# 2_cubesat_bus.net
KiCad netlist of a schematic drawn in Altium Designer
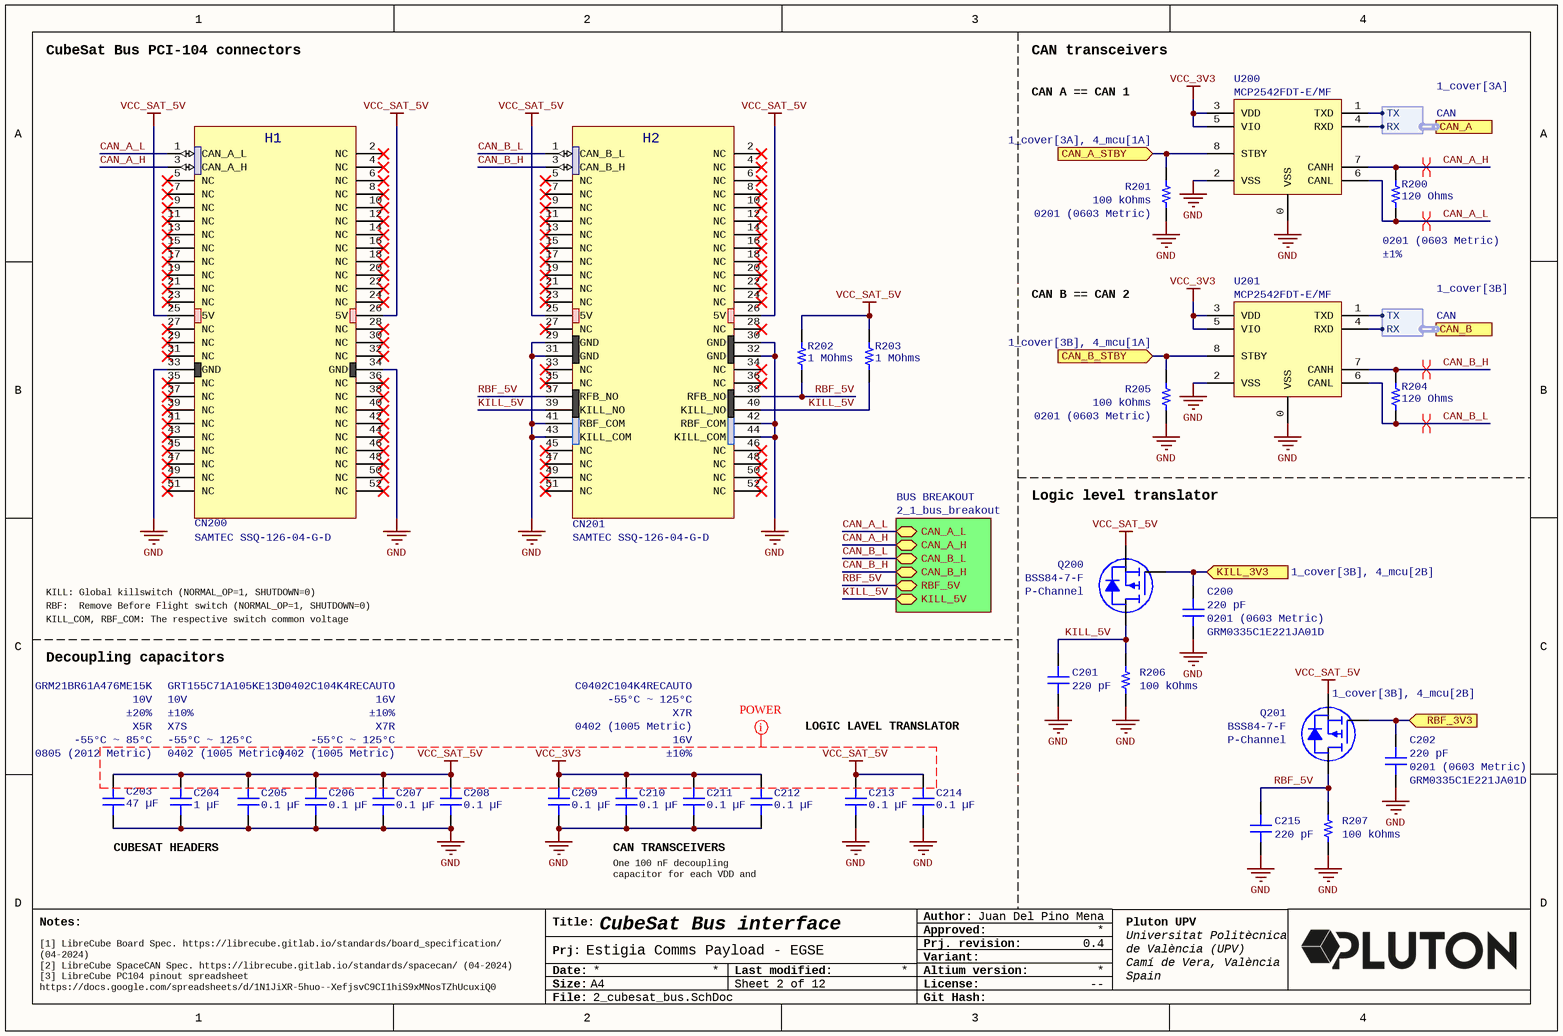
[diagram p0: 2_cubesat_bus.SchDoc]

(export (version "E")
  (design (tool "Eeschema 10.0.6"))
  (components
    (comp (ref "C200")
      (value "220 pF")
      (footprint "CAP 0201_0603")
      (description "CAP CER 220PF 25V C0G/NP0 0201")
      (fields
        (field (name "PART NUMBER") "GRM0335C1E221JA01D")
        (field (name "DEVICE PACKAGE") "0201 (0603 Metric)")
        (field (name "MANUFACTURER") "Murata Electronics")
        (field (name "TOLERANCE") "±5%")
      )
      (libsource (lib "Celestial Altium Library - altium_library") (part "Capacitor"))
    )
    (comp (ref "C201")
      (value "220 pF")
      (footprint "CAP 0201_0603")
      (description "CAP CER 220PF 25V C0G/NP0 0201")
      (fields
        (field (name "PART NUMBER") "GRM0335C1E221JA01D")
        (field (name "MANUFACTURER") "Murata Electronics")
      )
      (libsource (lib "Celestial Altium Library - altium_library") (part "Capacitor"))
    )
    (comp (ref "C202")
      (value "220 pF")
      (footprint "CAP 0201_0603")
      (description "CAP CER 220PF 25V C0G/NP0 0201")
      (fields
        (field (name "PART NUMBER") "GRM0335C1E221JA01D")
        (field (name "DEVICE PACKAGE") "0201 (0603 Metric)")
        (field (name "MANUFACTURER") "Murata Electronics")
        (field (name "TOLERANCE") "±5%")
      )
      (libsource (lib "Celestial Altium Library - altium_library") (part "Capacitor"))
    )
    (comp (ref "C203")
      (value "47 µF")
      (footprint "CAP 0805_2012")
      (description "CAP CER 47UF 10V X5R 0805")
      (fields
        (field (name "PART NUMBER") "GRM21BR61A476ME15K")
        (field (name "DEVICE PACKAGE") "0805 (2012 Metric)")
        (field (name "MANUFACTURER") "Murata Electronics")
        (field (name "OPERATING TEMPERATURE") "-55°C ~ 85°C")
        (field (name "TEMPERATURE COEFFICIENT") "X5R")
        (field (name "TOLERANCE") "±20%")
        (field (name "VOLTAGE - RATED") "10V")
      )
      (libsource (lib "Celestial Altium Library - altium_library") (part "Capacitor"))
    )
    (comp (ref "C204")
      (value "1 µF")
      (footprint "CAP 0402_1005")
      (description "CAP CER 1UF 10V X7S 0402")
      (fields
        (field (name "PART NUMBER") "GRT155C71A105KE13D")
        (field (name "DEVICE PACKAGE") "0402 (1005 Metric)")
        (field (name "MANUFACTURER") "Murata Electronics")
        (field (name "OPERATING TEMPERATURE") "-55°C ~ 125°C")
        (field (name "TEMPERATURE COEFFICIENT") "X7S")
        (field (name "TOLERANCE") "±10%")
        (field (name "VOLTAGE - RATED") "10V")
      )
      (libsource (lib "Celestial Altium Library - altium_library") (part "Capacitor"))
    )
    (comp (ref "C205")
      (value "0.1 µF")
      (footprint "CAP 0402_1005")
      (description "CAP CER 0402 0.1UF 16V X7R 10%")
      (fields
        (field (name "PART NUMBER") "C0402C104K4RECAUTO")
        (field (name "MANUFACTURER") "KEMET")
        (field (name "OPERATING TEMPERATURE") "-55°C ~ 125°C")
        (field (name "PACKAGE / CASE") "0402 (1005 Metric)")
        (field (name "TEMPERATURE COEFFICIENT") "X7R")
        (field (name "TOLERANCE") "±10%")
        (field (name "VOLTAGE - RATED") "16V")
      )
      (libsource (lib "Celestial Altium Library - altium_library") (part "Capacitor"))
    )
    (comp (ref "C206")
      (value "0.1 µF")
      (footprint "CAP 0402_1005")
      (description "CAP CER 0402 0.1UF 16V X7R 10%")
      (fields (field (name "PART NUMBER") "C0402C104K4RECAUTO") (field (name "MANUFACTURER") "KEMET"))
      (libsource (lib "Celestial Altium Library - altium_library") (part "Capacitor"))
    )
    (comp (ref "C207")
      (value "0.1 µF")
      (footprint "CAP 0402_1005")
      (description "CAP CER 0402 0.1UF 16V X7R 10%")
      (fields (field (name "PART NUMBER") "C0402C104K4RECAUTO") (field (name "MANUFACTURER") "KEMET"))
      (libsource (lib "Celestial Altium Library - altium_library") (part "Capacitor"))
    )
    (comp (ref "C208")
      (value "0.1 µF")
      (footprint "CAP 0402_1005")
      (description "CAP CER 0402 0.1UF 16V X7R 10%")
      (fields (field (name "PART NUMBER") "C0402C104K4RECAUTO") (field (name "MANUFACTURER") "KEMET"))
      (libsource (lib "Celestial Altium Library - altium_library") (part "Capacitor"))
    )
    (comp (ref "C209")
      (value "0.1 µF")
      (footprint "CAP 0402_1005")
      (description "CAP CER 0402 0.1UF 16V X7R 10%")
      (fields (field (name "PART NUMBER") "C0402C104K4RECAUTO") (field (name "MANUFACTURER") "KEMET"))
      (libsource (lib "Celestial Altium Library - altium_library") (part "Capacitor"))
    )
    (comp (ref "C210")
      (value "0.1 µF")
      (footprint "CAP 0402_1005")
      (description "CAP CER 0402 0.1UF 16V X7R 10%")
      (fields
        (field (name "PART NUMBER") "C0402C104K4RECAUTO")
        (field (name "MANUFACTURER") "KEMET")
        (field (name "OPERATING TEMPERATURE") "-55°C ~ 125°C")
        (field (name "PACKAGE / CASE") "0402 (1005 Metric)")
        (field (name "TEMPERATURE COEFFICIENT") "X7R")
        (field (name "TOLERANCE") "±10%")
        (field (name "VOLTAGE - RATED") "16V")
      )
      (libsource (lib "Celestial Altium Library - altium_library") (part "Capacitor"))
    )
    (comp (ref "C211")
      (value "0.1 µF")
      (footprint "CAP 0402_1005")
      (description "CAP CER 0402 0.1UF 16V X7R 10%")
      (fields (field (name "PART NUMBER") "C0402C104K4RECAUTO") (field (name "MANUFACTURER") "KEMET"))
      (libsource (lib "Celestial Altium Library - altium_library") (part "Capacitor"))
    )
    (comp (ref "C212")
      (value "0.1 µF")
      (footprint "CAP 0402_1005")
      (description "CAP CER 0402 0.1UF 16V X7R 10%")
      (fields (field (name "PART NUMBER") "C0402C104K4RECAUTO") (field (name "MANUFACTURER") "KEMET"))
      (libsource (lib "Celestial Altium Library - altium_library") (part "Capacitor"))
    )
    (comp (ref "C213")
      (value "0.1 µF")
      (footprint "CAP 0402_1005")
      (description "CAP CER 0402 0.1UF 16V X7R 10%")
      (fields (field (name "PART NUMBER") "C0402C104K4RECAUTO") (field (name "MANUFACTURER") "KEMET"))
      (libsource (lib "Celestial Altium Library - altium_library") (part "Capacitor"))
    )
    (comp (ref "C214")
      (value "0.1 µF")
      (footprint "CAP 0402_1005")
      (description "CAP CER 0402 0.1UF 16V X7R 10%")
      (fields (field (name "PART NUMBER") "C0402C104K4RECAUTO") (field (name "MANUFACTURER") "KEMET"))
      (libsource (lib "Celestial Altium Library - altium_library") (part "Capacitor"))
    )
    (comp (ref "C215")
      (value "220 pF")
      (footprint "CAP 0201_0603")
      (description "CAP CER 220PF 25V C0G/NP0 0201")
      (fields
        (field (name "PART NUMBER") "GRM0335C1E221JA01D")
        (field (name "MANUFACTURER") "Murata Electronics")
      )
      (libsource (lib "Celestial Altium Library - altium_library") (part "Capacitor"))
    )
    (comp (ref "CN200")
      (value "SAMTEC SSQ-126-04-G-D")
      (footprint "connectors:SAMTEC SSQ-126-04-G-D")
      (description "LoRa Payload only pins SAMTEC SSQ-126-04-G-D")
      (libsource (lib "cubesat_bus") (part "CubeSat Header H1 LoRa PL"))
    )
    (comp (ref "CN201")
      (value "SAMTEC SSQ-126-04-G-D")
      (footprint "connectors:SAMTEC SSQ-126-04-G-D")
      (description "LoRa Payload only pins")
      (libsource (lib "cubesat_bus") (part "CubeSat Header H2 LoRa PL"))
    )
    (comp (ref "Q200")
      (value "BSS84-7-F")
      (footprint "DIODES SOT-23-3")
      (description "MOSFET P-CH 50V 130MA SOT23-3")
      (fields
        (field (name "PART NUMBER") "BSS84-7-F")
        (field (name "FET TYPE") "P-Channel")
        (field (name "MANUFACTURER") "Diodes Incorporated")
      )
      (libsource (lib "Celestial Altium Library - altium_library") (part "DIODES MOSFET P-CH SOT-23-3"))
    )
    (comp (ref "Q201")
      (value "BSS84-7-F")
      (footprint "DIODES SOT-23-3")
      (description "MOSFET P-CH 50V 130MA SOT23-3")
      (fields
        (field (name "PART NUMBER") "BSS84-7-F")
        (field (name "FET TYPE") "P-Channel")
        (field (name "MANUFACTURER") "Diodes Incorporated")
      )
      (libsource (lib "Celestial Altium Library - altium_library") (part "DIODES MOSFET P-CH SOT-23-3"))
    )
    (comp (ref "R200")
      (value "120 Ohms")
      (footprint "RES 0201_0603")
      (description "RES SMD 120 OHM 1% 1/20W 0201")
      (fields
        (field (name "PART NUMBER") "CRCW0201120RFNED")
        (field (name "DEVICE PACKAGE") "0201 (0603 Metric)")
        (field (name "MANUFACTURER") "Vishay Dale")
        (field (name "TOLERANCE") "±1%")
      )
      (libsource (lib "Celestial Altium Library - altium_library") (part "Resistor"))
    )
    (comp (ref "R201")
      (value "100 kOhms")
      (footprint "RES 0201_0603")
      (description "RES 100K OHM 1% 1/20W 0201")
      (fields
        (field (name "PART NUMBER") "RC0201FR-13100KL")
        (field (name "DEVICE PACKAGE") "0201 (0603 Metric)")
        (field (name "MANUFACTURER") "Yageo")
      )
      (libsource (lib "Celestial Altium Library - altium_library") (part "Resistor"))
    )
    (comp (ref "R202")
      (value "1 MOhms")
      (footprint "RES 0201_0603")
      (description "RES SMD 1M OHM 5% 1/20W 0201")
      (fields (field (name "PART NUMBER") "CRCW02011M00JNED") (field (name "MANUFACTURER") "Vishay Dale"))
      (libsource (lib "Celestial Altium Library - altium_library") (part "Resistor"))
    )
    (comp (ref "R203")
      (value "1 MOhms")
      (footprint "RES 0201_0603")
      (description "RES SMD 1M OHM 5% 1/20W 0201")
      (fields (field (name "PART NUMBER") "CRCW02011M00JNED") (field (name "MANUFACTURER") "Vishay Dale"))
      (libsource (lib "Celestial Altium Library - altium_library") (part "Resistor"))
    )
    (comp (ref "R204")
      (value "120 Ohms")
      (footprint "RES 0201_0603")
      (description "RES SMD 120 OHM 1% 1/20W 0201")
      (fields (field (name "PART NUMBER") "CRCW0201120RFNED") (field (name "MANUFACTURER") "Vishay Dale"))
      (libsource (lib "Celestial Altium Library - altium_library") (part "Resistor"))
    )
    (comp (ref "R205")
      (value "100 kOhms")
      (footprint "RES 0201_0603")
      (description "RES 100K OHM 1% 1/20W 0201")
      (fields
        (field (name "PART NUMBER") "RC0201FR-13100KL")
        (field (name "DEVICE PACKAGE") "0201 (0603 Metric)")
        (field (name "MANUFACTURER") "Yageo")
      )
      (libsource (lib "Celestial Altium Library - altium_library") (part "Resistor"))
    )
    (comp (ref "R206")
      (value "100 kOhms")
      (footprint "RES 0201_0603")
      (description "RES 100K OHM 1% 1/20W 0201")
      (fields (field (name "PART NUMBER") "RC0201FR-13100KL") (field (name "MANUFACTURER") "Yageo"))
      (libsource (lib "Celestial Altium Library - altium_library") (part "Resistor"))
    )
    (comp (ref "R207")
      (value "100 kOhms")
      (footprint "RES 0201_0603")
      (description "RES 100K OHM 1% 1/20W 0201")
      (fields (field (name "PART NUMBER") "RC0201FR-13100KL") (field (name "MANUFACTURER") "Yageo"))
      (libsource (lib "Celestial Altium Library - altium_library") (part "Resistor"))
    )
    (comp (ref "U200")
      (value "MCP2542FDT-E/MF")
      (footprint "ics:DFN-8 3x3mm")
      (description "IC TRANSCEIVER 1/1 8DFN")
      (fields
        (field (name "MANUFACTURER") "Microchip Technology")
        (field (name "PART NUMBER") "MCP2542FDT-E/MF")
      )
      (libsource (lib "logic") (part "CAN MCP2542FDT-E/MF"))
    )
    (comp (ref "U201")
      (value "MCP2542FDT-E/MF")
      (footprint "ics:DFN-8 3x3mm")
      (description "IC TRANSCEIVER 1/1 8DFN")
      (fields
        (field (name "MANUFACTURER") "Microchip Technology")
        (field (name "PART NUMBER") "MCP2542FDT-E/MF")
      )
      (libsource (lib "logic") (part "CAN MCP2542FDT-E/MF"))
    )
  )
  (nets
    (net (code "2") (name "/CAN_A_H") (class "Default")
      (node (ref "CN200") (pin "3") (pinfunction "CAN_A_H_3") (pintype "bidirectional"))
      (node (ref "R200") (pin "2") (pinfunction "2_2") (pintype "passive"))
      (node (ref "U200") (pin "7") (pinfunction "CANH_7") (pintype "passive"))
    )
    (net (code "3") (name "/CAN_A_L") (class "Default")
      (node (ref "CN200") (pin "1") (pinfunction "CAN_A_L_1") (pintype "bidirectional"))
      (node (ref "R200") (pin "1") (pinfunction "1_1") (pintype "passive"))
      (node (ref "U200") (pin "6") (pinfunction "CANL_6") (pintype "passive"))
    )
    (net (code "4") (name "/CAN_A_STBY") (class "Default")
      (node (ref "R201") (pin "2") (pinfunction "2_2") (pintype "passive"))
      (node (ref "U200") (pin "8") (pinfunction "STBY_8") (pintype "passive"))
    )
    (net (code "5") (name "/CAN_B_H") (class "Default")
      (node (ref "CN201") (pin "3") (pinfunction "CAN_B_H_3") (pintype "bidirectional"))
      (node (ref "R204") (pin "2") (pinfunction "2_2") (pintype "passive"))
      (node (ref "U201") (pin "7") (pinfunction "CANH_7") (pintype "passive"))
    )
    (net (code "6") (name "/CAN_B_L") (class "Default")
      (node (ref "CN201") (pin "1") (pinfunction "CAN_B_L_1") (pintype "bidirectional"))
      (node (ref "R204") (pin "1") (pinfunction "1_1") (pintype "passive"))
      (node (ref "U201") (pin "6") (pinfunction "CANL_6") (pintype "passive"))
    )
    (net (code "7") (name "/CAN_B_STBY") (class "Default")
      (node (ref "R205") (pin "2") (pinfunction "2_2") (pintype "passive"))
      (node (ref "U201") (pin "8") (pinfunction "STBY_8") (pintype "passive"))
    )
    (net (code "8") (name "/KILL_3V3") (class "Default")
      (node (ref "C200") (pin "2") (pinfunction "2_2") (pintype "passive"))
      (node (ref "Q200") (pin "1") (pinfunction "G_1") (pintype "passive"))
    )
    (net (code "9") (name "/KILL_5V") (class "Default")
      (node (ref "C201") (pin "2") (pinfunction "2_2") (pintype "passive"))
      (node (ref "CN201") (pin "39") (pinfunction "KILL_NO_39") (pintype "passive"))
      (node (ref "CN201") (pin "40") (pinfunction "KILL_NO_40") (pintype "passive"))
      (node (ref "Q200") (pin "3") (pinfunction "D_3") (pintype "passive"))
      (node (ref "R203") (pin "1") (pinfunction "1_1") (pintype "passive"))
      (node (ref "R206") (pin "1") (pinfunction "1_1") (pintype "passive"))
    )
    (net (code "10") (name "/RBF_3V3") (class "Default")
      (node (ref "C202") (pin "2") (pinfunction "2_2") (pintype "passive"))
      (node (ref "Q201") (pin "1") (pinfunction "G_1") (pintype "passive"))
    )
    (net (code "11") (name "/RBF_5V") (class "Default")
      (node (ref "C215") (pin "2") (pinfunction "2_2") (pintype "passive"))
      (node (ref "CN201") (pin "37") (pinfunction "RFB_NO_37") (pintype "passive"))
      (node (ref "CN201") (pin "38") (pinfunction "RFB_NO_38") (pintype "passive"))
      (node (ref "Q201") (pin "3") (pinfunction "D_3") (pintype "passive"))
      (node (ref "R202") (pin "1") (pinfunction "1_1") (pintype "passive"))
      (node (ref "R207") (pin "1") (pinfunction "1_1") (pintype "passive"))
    )
    (net (code "13") (name "GND") (class "Default")
      (node (ref "C200") (pin "1") (pinfunction "1_1") (pintype "passive"))
      (node (ref "C201") (pin "1") (pinfunction "1_1") (pintype "passive"))
      (node (ref "C202") (pin "1") (pinfunction "1_1") (pintype "passive"))
      (node (ref "C203") (pin "1") (pinfunction "1_1") (pintype "passive"))
      (node (ref "C204") (pin "1") (pinfunction "1_1") (pintype "passive"))
      (node (ref "C205") (pin "1") (pinfunction "1_1") (pintype "passive"))
      (node (ref "C206") (pin "1") (pinfunction "1_1") (pintype "passive"))
      (node (ref "C207") (pin "1") (pinfunction "1_1") (pintype "passive"))
      (node (ref "C208") (pin "1") (pinfunction "1_1") (pintype "passive"))
      (node (ref "C209") (pin "1") (pinfunction "1_1") (pintype "passive"))
      (node (ref "C210") (pin "1") (pinfunction "1_1") (pintype "passive"))
      (node (ref "C211") (pin "1") (pinfunction "1_1") (pintype "passive"))
      (node (ref "C212") (pin "1") (pinfunction "1_1") (pintype "passive"))
      (node (ref "C213") (pin "1") (pinfunction "1_1") (pintype "passive"))
      (node (ref "C214") (pin "1") (pinfunction "1_1") (pintype "passive"))
      (node (ref "C215") (pin "1") (pinfunction "1_1") (pintype "passive"))
      (node (ref "CN200") (pin "33") (pinfunction "GND_33") (pintype "power_in"))
      (node (ref "CN200") (pin "34") (pinfunction "GND_34") (pintype "power_in"))
      (node (ref "CN201") (pin "29") (pinfunction "GND_29") (pintype "power_in"))
      (node (ref "CN201") (pin "30") (pinfunction "GND_30") (pintype "power_in"))
      (node (ref "CN201") (pin "31") (pinfunction "GND_31") (pintype "power_in"))
      (node (ref "CN201") (pin "32") (pinfunction "GND_32") (pintype "power_in"))
      (node (ref "CN201") (pin "41") (pinfunction "RBF_COM_41") (pintype "passive"))
      (node (ref "CN201") (pin "42") (pinfunction "RBF_COM_42") (pintype "passive"))
      (node (ref "CN201") (pin "43") (pinfunction "KILL_COM_43") (pintype "passive"))
      (node (ref "CN201") (pin "44") (pinfunction "KILL_COM_44") (pintype "passive"))
      (node (ref "R201") (pin "1") (pinfunction "1_1") (pintype "passive"))
      (node (ref "R205") (pin "1") (pinfunction "1_1") (pintype "passive"))
      (node (ref "R206") (pin "2") (pinfunction "2_2") (pintype "passive"))
      (node (ref "R207") (pin "2") (pinfunction "2_2") (pintype "passive"))
      (node (ref "U200") (pin "0") (pinfunction "VSS_0") (pintype "passive"))
      (node (ref "U200") (pin "2") (pinfunction "VSS_2") (pintype "passive"))
      (node (ref "U201") (pin "0") (pinfunction "VSS_0") (pintype "passive"))
      (node (ref "U201") (pin "2") (pinfunction "VSS_2") (pintype "passive"))
    )
    (net (code "14") (name "VCC_3V3") (class "Default")
      (node (ref "C209") (pin "2") (pinfunction "2_2") (pintype "passive"))
      (node (ref "C210") (pin "2") (pinfunction "2_2") (pintype "passive"))
      (node (ref "C211") (pin "2") (pinfunction "2_2") (pintype "passive"))
      (node (ref "C212") (pin "2") (pinfunction "2_2") (pintype "passive"))
      (node (ref "U200") (pin "3") (pinfunction "VDD_3") (pintype "passive"))
      (node (ref "U200") (pin "5") (pinfunction "VIO_5") (pintype "passive"))
      (node (ref "U201") (pin "3") (pinfunction "VDD_3") (pintype "passive"))
      (node (ref "U201") (pin "5") (pinfunction "VIO_5") (pintype "passive"))
    )
    (net (code "15") (name "VCC_SAT_5V") (class "Default")
      (node (ref "C203") (pin "2") (pinfunction "2_2") (pintype "passive"))
      (node (ref "C204") (pin "2") (pinfunction "2_2") (pintype "passive"))
      (node (ref "C205") (pin "2") (pinfunction "2_2") (pintype "passive"))
      (node (ref "C206") (pin "2") (pinfunction "2_2") (pintype "passive"))
      (node (ref "C207") (pin "2") (pinfunction "2_2") (pintype "passive"))
      (node (ref "C208") (pin "2") (pinfunction "2_2") (pintype "passive"))
      (node (ref "C213") (pin "2") (pinfunction "2_2") (pintype "passive"))
      (node (ref "C214") (pin "2") (pinfunction "2_2") (pintype "passive"))
      (node (ref "CN200") (pin "25") (pinfunction "5V_25") (pintype "power_in"))
      (node (ref "CN200") (pin "26") (pinfunction "5V_26") (pintype "power_in"))
      (node (ref "CN201") (pin "25") (pinfunction "5V_25") (pintype "power_in"))
      (node (ref "CN201") (pin "26") (pinfunction "5V_26") (pintype "power_in"))
      (node (ref "Q200") (pin "2") (pinfunction "S_2") (pintype "passive"))
      (node (ref "Q201") (pin "2") (pinfunction "S_2") (pintype "passive"))
      (node (ref "R202") (pin "2") (pinfunction "2_2") (pintype "passive"))
      (node (ref "R203") (pin "2") (pinfunction "2_2") (pintype "passive"))
    )
    (net (code "16") (name "unconnected-(CN200-NC-Pad2)") (class "Default")
      (node (ref "CN200") (pin "2") (pinfunction "NC_2") (pintype "passive+no_connect"))
    )
    (net (code "17") (name "unconnected-(CN200-NC-Pad4)") (class "Default")
      (node (ref "CN200") (pin "4") (pinfunction "NC_4") (pintype "passive+no_connect"))
    )
    (net (code "18") (name "unconnected-(CN200-NC-Pad5)") (class "Default")
      (node (ref "CN200") (pin "5") (pinfunction "NC_5") (pintype "passive+no_connect"))
    )
    (net (code "19") (name "unconnected-(CN200-NC-Pad6)") (class "Default")
      (node (ref "CN200") (pin "6") (pinfunction "NC_6") (pintype "passive+no_connect"))
    )
    (net (code "20") (name "unconnected-(CN200-NC-Pad7)") (class "Default")
      (node (ref "CN200") (pin "7") (pinfunction "NC_7") (pintype "passive+no_connect"))
    )
    (net (code "21") (name "unconnected-(CN200-NC-Pad8)") (class "Default")
      (node (ref "CN200") (pin "8") (pinfunction "NC_8") (pintype "passive+no_connect"))
    )
    (net (code "22") (name "unconnected-(CN200-NC-Pad9)") (class "Default")
      (node (ref "CN200") (pin "9") (pinfunction "NC_9") (pintype "passive+no_connect"))
    )
    (net (code "23") (name "unconnected-(CN200-NC-Pad10)") (class "Default")
      (node (ref "CN200") (pin "10") (pinfunction "NC_10") (pintype "passive+no_connect"))
    )
    (net (code "24") (name "unconnected-(CN200-NC-Pad11)") (class "Default")
      (node (ref "CN200") (pin "11") (pinfunction "NC_11") (pintype "passive+no_connect"))
    )
    (net (code "25") (name "unconnected-(CN200-NC-Pad12)") (class "Default")
      (node (ref "CN200") (pin "12") (pinfunction "NC_12") (pintype "passive+no_connect"))
    )
    (net (code "26") (name "unconnected-(CN200-NC-Pad13)") (class "Default")
      (node (ref "CN200") (pin "13") (pinfunction "NC_13") (pintype "passive+no_connect"))
    )
    (net (code "27") (name "unconnected-(CN200-NC-Pad14)") (class "Default")
      (node (ref "CN200") (pin "14") (pinfunction "NC_14") (pintype "passive+no_connect"))
    )
    (net (code "28") (name "unconnected-(CN200-NC-Pad15)") (class "Default")
      (node (ref "CN200") (pin "15") (pinfunction "NC_15") (pintype "passive+no_connect"))
    )
    (net (code "29") (name "unconnected-(CN200-NC-Pad16)") (class "Default")
      (node (ref "CN200") (pin "16") (pinfunction "NC_16") (pintype "passive+no_connect"))
    )
    (net (code "30") (name "unconnected-(CN200-NC-Pad17)") (class "Default")
      (node (ref "CN200") (pin "17") (pinfunction "NC_17") (pintype "passive+no_connect"))
    )
    (net (code "31") (name "unconnected-(CN200-NC-Pad18)") (class "Default")
      (node (ref "CN200") (pin "18") (pinfunction "NC_18") (pintype "passive+no_connect"))
    )
    (net (code "32") (name "unconnected-(CN200-NC-Pad19)") (class "Default")
      (node (ref "CN200") (pin "19") (pinfunction "NC_19") (pintype "passive+no_connect"))
    )
    (net (code "33") (name "unconnected-(CN200-NC-Pad20)") (class "Default")
      (node (ref "CN200") (pin "20") (pinfunction "NC_20") (pintype "passive+no_connect"))
    )
    (net (code "34") (name "unconnected-(CN200-NC-Pad21)") (class "Default")
      (node (ref "CN200") (pin "21") (pinfunction "NC_21") (pintype "passive+no_connect"))
    )
    (net (code "35") (name "unconnected-(CN200-NC-Pad22)") (class "Default")
      (node (ref "CN200") (pin "22") (pinfunction "NC_22") (pintype "passive+no_connect"))
    )
    (net (code "36") (name "unconnected-(CN200-NC-Pad23)") (class "Default")
      (node (ref "CN200") (pin "23") (pinfunction "NC_23") (pintype "passive+no_connect"))
    )
    (net (code "37") (name "unconnected-(CN200-NC-Pad24)") (class "Default")
      (node (ref "CN200") (pin "24") (pinfunction "NC_24") (pintype "passive+no_connect"))
    )
    (net (code "38") (name "unconnected-(CN200-NC-Pad27)") (class "Default")
      (node (ref "CN200") (pin "27") (pinfunction "NC_27") (pintype "passive+no_connect"))
    )
    (net (code "39") (name "unconnected-(CN200-NC-Pad28)") (class "Default")
      (node (ref "CN200") (pin "28") (pinfunction "NC_28") (pintype "passive+no_connect"))
    )
    (net (code "40") (name "unconnected-(CN200-NC-Pad29)") (class "Default")
      (node (ref "CN200") (pin "29") (pinfunction "NC_29") (pintype "passive+no_connect"))
    )
    (net (code "41") (name "unconnected-(CN200-NC-Pad30)") (class "Default")
      (node (ref "CN200") (pin "30") (pinfunction "NC_30") (pintype "passive+no_connect"))
    )
    (net (code "42") (name "unconnected-(CN200-NC-Pad31)") (class "Default")
      (node (ref "CN200") (pin "31") (pinfunction "NC_31") (pintype "passive+no_connect"))
    )
    (net (code "43") (name "unconnected-(CN200-NC-Pad32)") (class "Default")
      (node (ref "CN200") (pin "32") (pinfunction "NC_32") (pintype "passive+no_connect"))
    )
    (net (code "44") (name "unconnected-(CN200-NC-Pad35)") (class "Default")
      (node (ref "CN200") (pin "35") (pinfunction "NC_35") (pintype "passive+no_connect"))
    )
    (net (code "45") (name "unconnected-(CN200-NC-Pad36)") (class "Default")
      (node (ref "CN200") (pin "36") (pinfunction "NC_36") (pintype "passive+no_connect"))
    )
    (net (code "46") (name "unconnected-(CN200-NC-Pad37)") (class "Default")
      (node (ref "CN200") (pin "37") (pinfunction "NC_37") (pintype "passive+no_connect"))
    )
    (net (code "47") (name "unconnected-(CN200-NC-Pad38)") (class "Default")
      (node (ref "CN200") (pin "38") (pinfunction "NC_38") (pintype "passive+no_connect"))
    )
    (net (code "48") (name "unconnected-(CN200-NC-Pad39)") (class "Default")
      (node (ref "CN200") (pin "39") (pinfunction "NC_39") (pintype "passive+no_connect"))
    )
    (net (code "49") (name "unconnected-(CN200-NC-Pad40)") (class "Default")
      (node (ref "CN200") (pin "40") (pinfunction "NC_40") (pintype "passive+no_connect"))
    )
    (net (code "50") (name "unconnected-(CN200-NC-Pad41)") (class "Default")
      (node (ref "CN200") (pin "41") (pinfunction "NC_41") (pintype "passive+no_connect"))
    )
    (net (code "51") (name "unconnected-(CN200-NC-Pad42)") (class "Default")
      (node (ref "CN200") (pin "42") (pinfunction "NC_42") (pintype "passive+no_connect"))
    )
    (net (code "52") (name "unconnected-(CN200-NC-Pad43)") (class "Default")
      (node (ref "CN200") (pin "43") (pinfunction "NC_43") (pintype "passive+no_connect"))
    )
    (net (code "53") (name "unconnected-(CN200-NC-Pad44)") (class "Default")
      (node (ref "CN200") (pin "44") (pinfunction "NC_44") (pintype "passive+no_connect"))
    )
    (net (code "54") (name "unconnected-(CN200-NC-Pad45)") (class "Default")
      (node (ref "CN200") (pin "45") (pinfunction "NC_45") (pintype "passive+no_connect"))
    )
    (net (code "55") (name "unconnected-(CN200-NC-Pad46)") (class "Default")
      (node (ref "CN200") (pin "46") (pinfunction "NC_46") (pintype "passive+no_connect"))
    )
    (net (code "56") (name "unconnected-(CN200-NC-Pad47)") (class "Default")
      (node (ref "CN200") (pin "47") (pinfunction "NC_47") (pintype "passive+no_connect"))
    )
    (net (code "57") (name "unconnected-(CN200-NC-Pad48)") (class "Default")
      (node (ref "CN200") (pin "48") (pinfunction "NC_48") (pintype "passive+no_connect"))
    )
    (net (code "58") (name "unconnected-(CN200-NC-Pad49)") (class "Default")
      (node (ref "CN200") (pin "49") (pinfunction "NC_49") (pintype "passive+no_connect"))
    )
    (net (code "59") (name "unconnected-(CN200-NC-Pad50)") (class "Default")
      (node (ref "CN200") (pin "50") (pinfunction "NC_50") (pintype "passive+no_connect"))
    )
    (net (code "60") (name "unconnected-(CN200-NC-Pad51)") (class "Default")
      (node (ref "CN200") (pin "51") (pinfunction "NC_51") (pintype "passive+no_connect"))
    )
    (net (code "61") (name "unconnected-(CN200-NC-Pad52)") (class "Default")
      (node (ref "CN200") (pin "52") (pinfunction "NC_52") (pintype "passive+no_connect"))
    )
    (net (code "62") (name "unconnected-(CN201-NC-Pad2)") (class "Default")
      (node (ref "CN201") (pin "2") (pinfunction "NC_2") (pintype "passive+no_connect"))
    )
    (net (code "63") (name "unconnected-(CN201-NC-Pad4)") (class "Default")
      (node (ref "CN201") (pin "4") (pinfunction "NC_4") (pintype "passive+no_connect"))
    )
    (net (code "64") (name "unconnected-(CN201-NC-Pad5)") (class "Default")
      (node (ref "CN201") (pin "5") (pinfunction "NC_5") (pintype "passive+no_connect"))
    )
    (net (code "65") (name "unconnected-(CN201-NC-Pad6)") (class "Default")
      (node (ref "CN201") (pin "6") (pinfunction "NC_6") (pintype "passive+no_connect"))
    )
    (net (code "66") (name "unconnected-(CN201-NC-Pad7)") (class "Default")
      (node (ref "CN201") (pin "7") (pinfunction "NC_7") (pintype "passive+no_connect"))
    )
    (net (code "67") (name "unconnected-(CN201-NC-Pad8)") (class "Default")
      (node (ref "CN201") (pin "8") (pinfunction "NC_8") (pintype "passive+no_connect"))
    )
    (net (code "68") (name "unconnected-(CN201-NC-Pad9)") (class "Default")
      (node (ref "CN201") (pin "9") (pinfunction "NC_9") (pintype "passive+no_connect"))
    )
    (net (code "69") (name "unconnected-(CN201-NC-Pad10)") (class "Default")
      (node (ref "CN201") (pin "10") (pinfunction "NC_10") (pintype "passive+no_connect"))
    )
    (net (code "70") (name "unconnected-(CN201-NC-Pad11)") (class "Default")
      (node (ref "CN201") (pin "11") (pinfunction "NC_11") (pintype "passive+no_connect"))
    )
    (net (code "71") (name "unconnected-(CN201-NC-Pad12)") (class "Default")
      (node (ref "CN201") (pin "12") (pinfunction "NC_12") (pintype "passive+no_connect"))
    )
    (net (code "72") (name "unconnected-(CN201-NC-Pad13)") (class "Default")
      (node (ref "CN201") (pin "13") (pinfunction "NC_13") (pintype "passive+no_connect"))
    )
    (net (code "73") (name "unconnected-(CN201-NC-Pad14)") (class "Default")
      (node (ref "CN201") (pin "14") (pinfunction "NC_14") (pintype "passive+no_connect"))
    )
    (net (code "74") (name "unconnected-(CN201-NC-Pad15)") (class "Default")
      (node (ref "CN201") (pin "15") (pinfunction "NC_15") (pintype "passive+no_connect"))
    )
    (net (code "75") (name "unconnected-(CN201-NC-Pad16)") (class "Default")
      (node (ref "CN201") (pin "16") (pinfunction "NC_16") (pintype "passive+no_connect"))
    )
    (net (code "76") (name "unconnected-(CN201-NC-Pad17)") (class "Default")
      (node (ref "CN201") (pin "17") (pinfunction "NC_17") (pintype "passive+no_connect"))
    )
    (net (code "77") (name "unconnected-(CN201-NC-Pad18)") (class "Default")
      (node (ref "CN201") (pin "18") (pinfunction "NC_18") (pintype "passive+no_connect"))
    )
    (net (code "78") (name "unconnected-(CN201-NC-Pad19)") (class "Default")
      (node (ref "CN201") (pin "19") (pinfunction "NC_19") (pintype "passive+no_connect"))
    )
    (net (code "79") (name "unconnected-(CN201-NC-Pad20)") (class "Default")
      (node (ref "CN201") (pin "20") (pinfunction "NC_20") (pintype "passive+no_connect"))
    )
    (net (code "80") (name "unconnected-(CN201-NC-Pad21)") (class "Default")
      (node (ref "CN201") (pin "21") (pinfunction "NC_21") (pintype "passive+no_connect"))
    )
    (net (code "81") (name "unconnected-(CN201-NC-Pad22)") (class "Default")
      (node (ref "CN201") (pin "22") (pinfunction "NC_22") (pintype "passive+no_connect"))
    )
    (net (code "82") (name "unconnected-(CN201-NC-Pad23)") (class "Default")
      (node (ref "CN201") (pin "23") (pinfunction "NC_23") (pintype "passive+no_connect"))
    )
    (net (code "83") (name "unconnected-(CN201-NC-Pad24)") (class "Default")
      (node (ref "CN201") (pin "24") (pinfunction "NC_24") (pintype "passive+no_connect"))
    )
    (net (code "84") (name "unconnected-(CN201-NC-Pad27)") (class "Default")
      (node (ref "CN201") (pin "27") (pinfunction "NC_27") (pintype "passive+no_connect"))
    )
    (net (code "85") (name "unconnected-(CN201-NC-Pad28)") (class "Default")
      (node (ref "CN201") (pin "28") (pinfunction "NC_28") (pintype "passive+no_connect"))
    )
    (net (code "86") (name "unconnected-(CN201-NC-Pad33)") (class "Default")
      (node (ref "CN201") (pin "33") (pinfunction "NC_33") (pintype "passive+no_connect"))
    )
    (net (code "87") (name "unconnected-(CN201-NC-Pad34)") (class "Default")
      (node (ref "CN201") (pin "34") (pinfunction "NC_34") (pintype "passive+no_connect"))
    )
    (net (code "88") (name "unconnected-(CN201-NC-Pad35)") (class "Default")
      (node (ref "CN201") (pin "35") (pinfunction "NC_35") (pintype "passive+no_connect"))
    )
    (net (code "89") (name "unconnected-(CN201-NC-Pad36)") (class "Default")
      (node (ref "CN201") (pin "36") (pinfunction "NC_36") (pintype "passive+no_connect"))
    )
    (net (code "90") (name "unconnected-(CN201-NC-Pad45)") (class "Default")
      (node (ref "CN201") (pin "45") (pinfunction "NC_45") (pintype "power_in+no_connect"))
    )
    (net (code "91") (name "unconnected-(CN201-NC-Pad46)") (class "Default")
      (node (ref "CN201") (pin "46") (pinfunction "NC_46") (pintype "power_in+no_connect"))
    )
    (net (code "92") (name "unconnected-(CN201-NC-Pad47)") (class "Default")
      (node (ref "CN201") (pin "47") (pinfunction "NC_47") (pintype "passive+no_connect"))
    )
    (net (code "93") (name "unconnected-(CN201-NC-Pad48)") (class "Default")
      (node (ref "CN201") (pin "48") (pinfunction "NC_48") (pintype "passive+no_connect"))
    )
    (net (code "94") (name "unconnected-(CN201-NC-Pad49)") (class "Default")
      (node (ref "CN201") (pin "49") (pinfunction "NC_49") (pintype "passive+no_connect"))
    )
    (net (code "95") (name "unconnected-(CN201-NC-Pad50)") (class "Default")
      (node (ref "CN201") (pin "50") (pinfunction "NC_50") (pintype "passive+no_connect"))
    )
    (net (code "96") (name "unconnected-(CN201-NC-Pad51)") (class "Default")
      (node (ref "CN201") (pin "51") (pinfunction "NC_51") (pintype "passive+no_connect"))
    )
    (net (code "97") (name "unconnected-(CN201-NC-Pad52)") (class "Default")
      (node (ref "CN201") (pin "52") (pinfunction "NC_52") (pintype "passive+no_connect"))
    )
    (net (code "98") (name "unconnected-(U200-RXD-Pad4)") (class "Default")
      (node (ref "U200") (pin "4") (pinfunction "RXD_4") (pintype "passive"))
    )
    (net (code "99") (name "unconnected-(U200-TXD-Pad1)") (class "Default")
      (node (ref "U200") (pin "1") (pinfunction "TXD_1") (pintype "passive"))
    )
    (net (code "100") (name "unconnected-(U201-RXD-Pad4)") (class "Default")
      (node (ref "U201") (pin "4") (pinfunction "RXD_4") (pintype "passive"))
    )
    (net (code "101") (name "unconnected-(U201-TXD-Pad1)") (class "Default")
      (node (ref "U201") (pin "1") (pinfunction "TXD_1") (pintype "passive"))
    )
  )
)
